# ProProject__PCB_2024-01-29.net
KiCad netlist of a schematic drawn in EasyEDA Pro
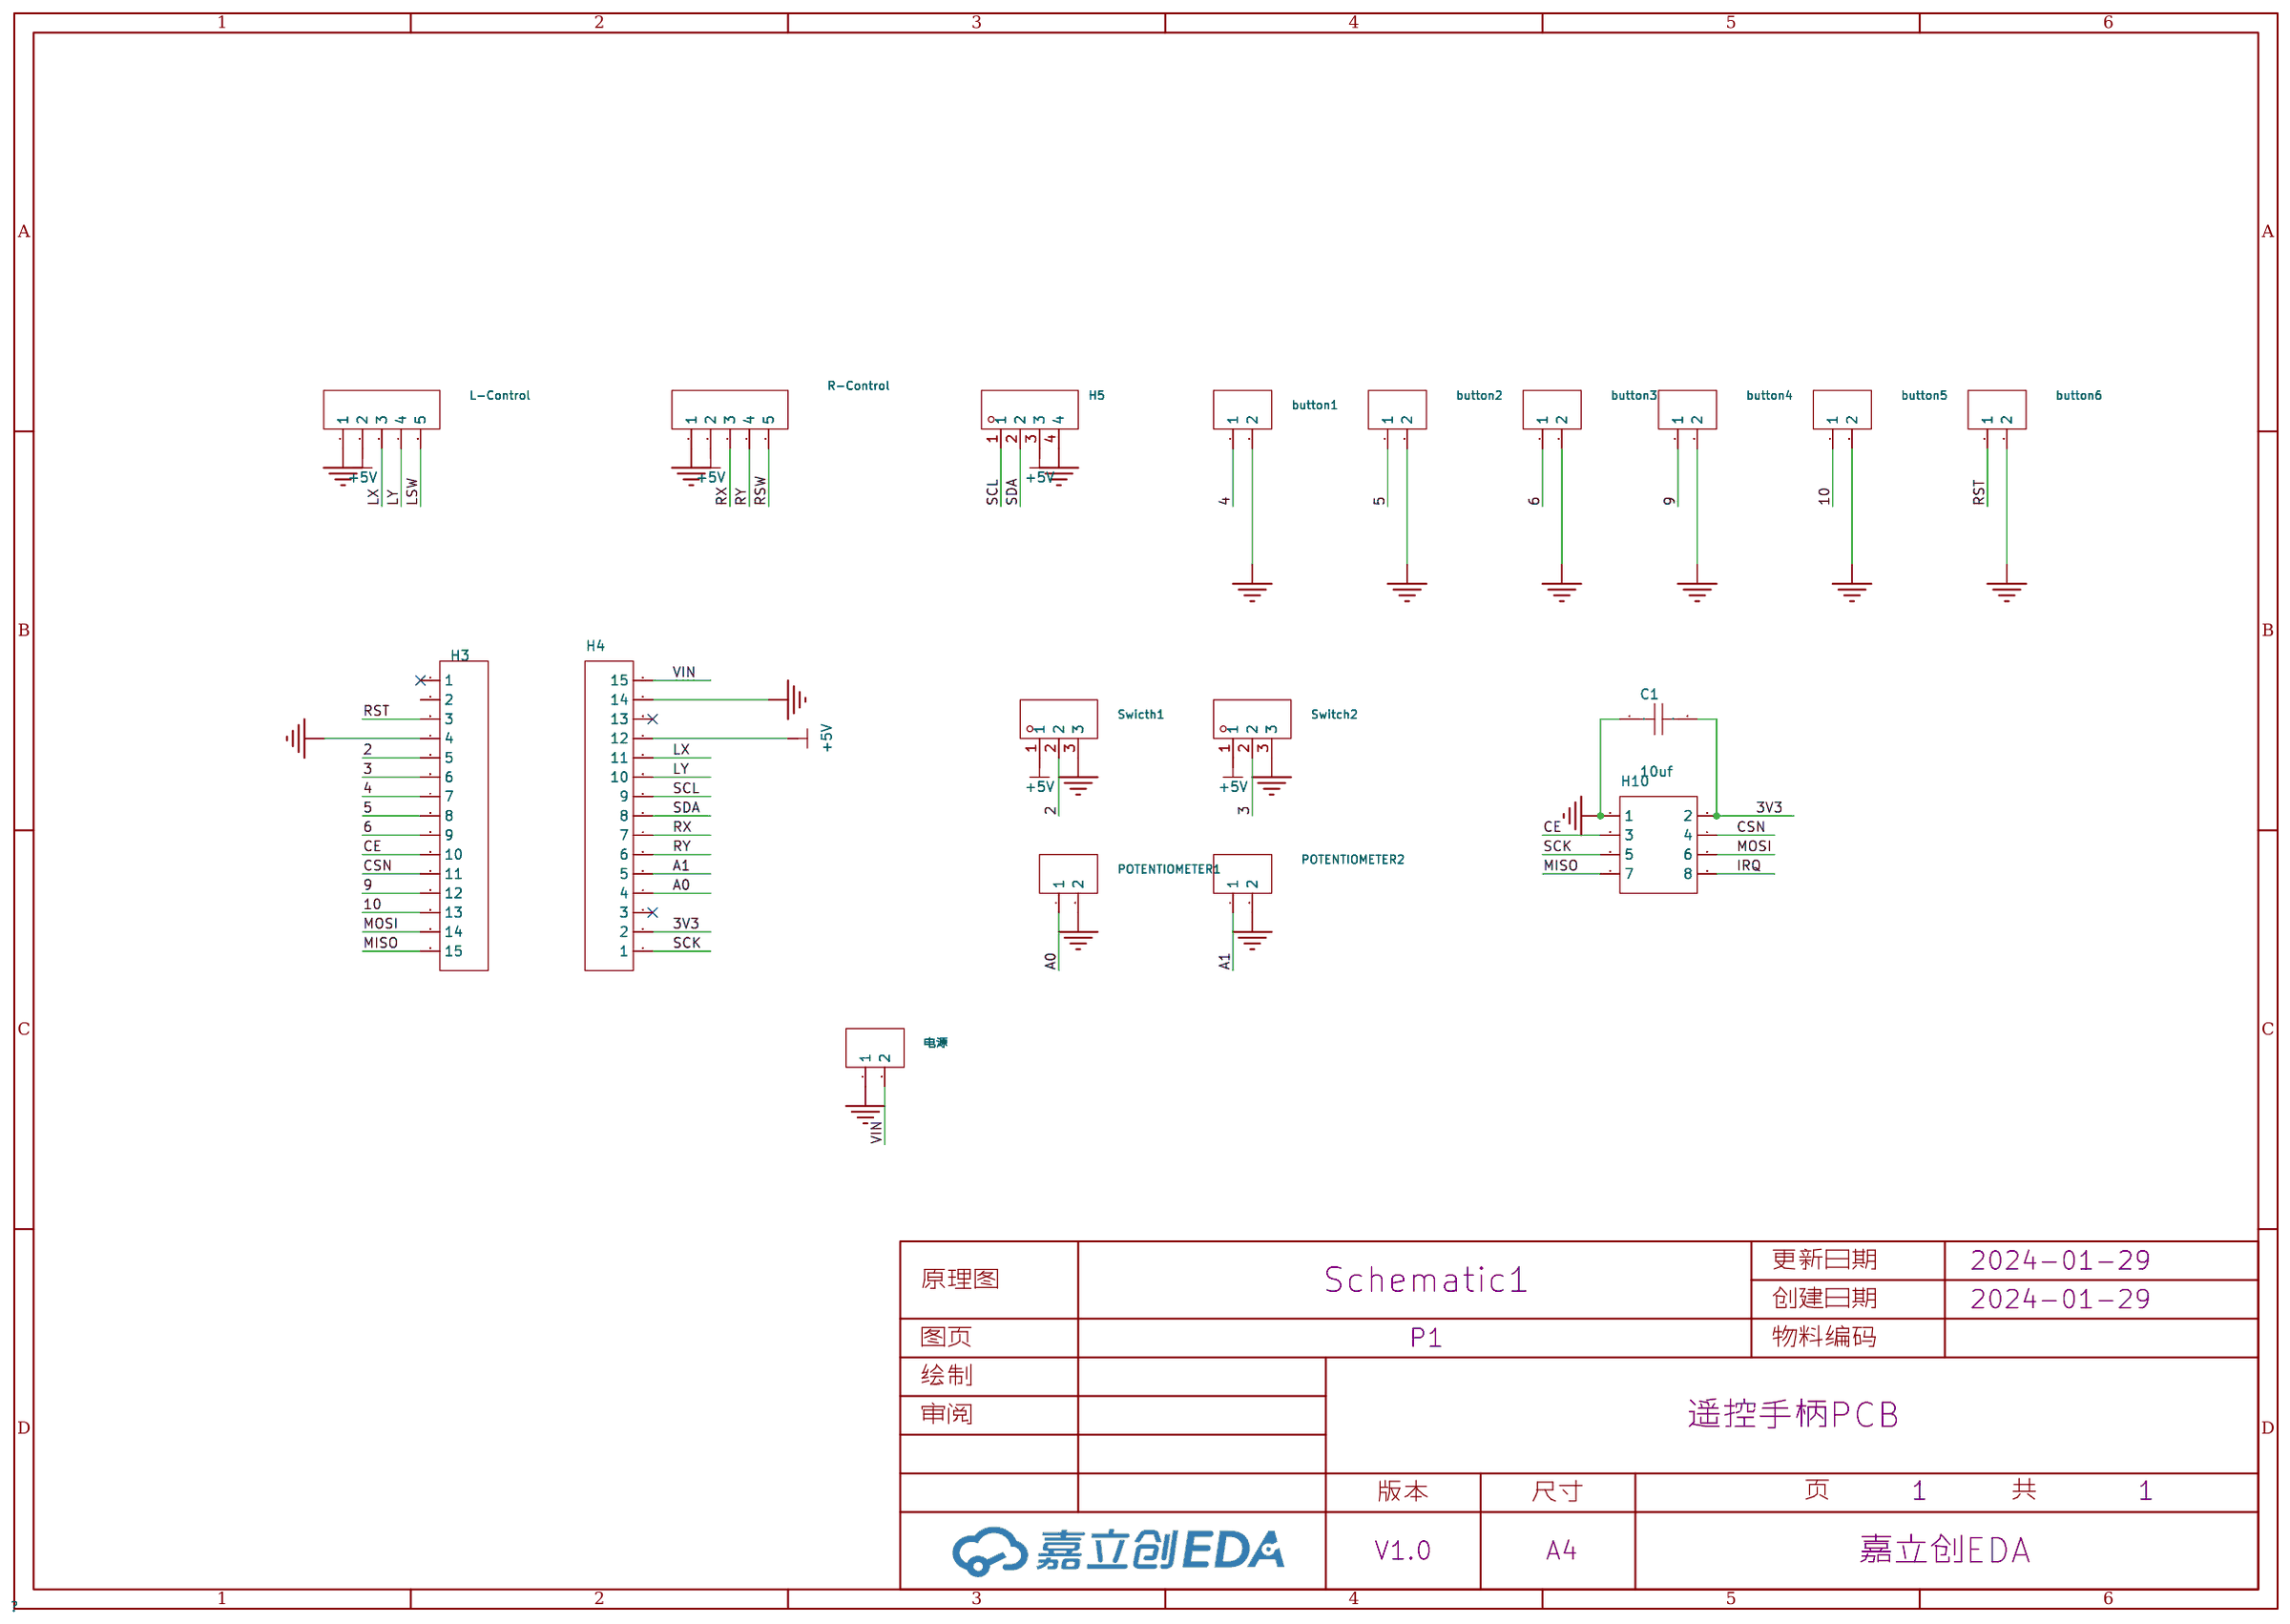
[diagram p0: schematic sheet]

(export (version "E")
  (design (tool "Eeschema 10.0.6"))
  (components
    (comp (ref "button1")
      (value "~")
      (footprint "easyedapro:HDR-TH_2P-P2.54-V-F")
      (libsource (lib "easyedapro") (part "Header-Female-2.54_1x2"))
    )
    (comp (ref "button2")
      (value "~")
      (footprint "easyedapro:HDR-TH_2P-P2.54-V-F")
      (libsource (lib "easyedapro") (part "Header-Female-2.54_1x2"))
    )
    (comp (ref "button3")
      (value "~")
      (footprint "easyedapro:HDR-TH_2P-P2.54-V-F")
      (libsource (lib "easyedapro") (part "Header-Female-2.54_1x2"))
    )
    (comp (ref "button4")
      (value "~")
      (footprint "easyedapro:HDR-TH_2P-P2.54-V-F")
      (libsource (lib "easyedapro") (part "Header-Female-2.54_1x2"))
    )
    (comp (ref "button5")
      (value "~")
      (footprint "easyedapro:HDR-TH_2P-P2.54-V-F")
      (libsource (lib "easyedapro") (part "Header-Female-2.54_1x2"))
    )
    (comp (ref "button6")
      (value "~")
      (footprint "easyedapro:HDR-TH_2P-P2.54-V-F")
      (libsource (lib "easyedapro") (part "Header-Female-2.54_1x2"))
    )
    (comp (ref "C1")
      (value "10uf")
      (footprint "easyedapro:C0805")
      (libsource (lib "easyedapro") (part "CapAcitance"))
    )
    (comp (ref "H3")
      (value "~")
      (footprint "easyedapro:HDR-TH_15P-P2.54-V-F-1")
      (libsource (lib "easyedapro") (part "HDR-F_2.54_1x15P"))
    )
    (comp (ref "H4")
      (value "~")
      (footprint "easyedapro:HDR-TH_15P-P2.54-V-F-1")
      (libsource (lib "easyedapro") (part "HDR-F_2.54_1x15P"))
    )
    (comp (ref "H5")
      (value "~")
      (footprint "easyedapro:HDR-TH_4P-P2.54-V-F")
      (libsource (lib "easyedapro") (part "2.54-1*4P母"))
    )
    (comp (ref "H10")
      (value "~")
      (footprint "easyedapro:HDR-TH_8P-P2.54-V-F-R2-C4-S2.54-1")
      (libsource (lib "easyedapro") (part "HDR-F-2.54_2x4"))
    )
    (comp (ref "L-Control")
      (value "~")
      (footprint "easyedapro:HDR-TH_5P-P2.54-V-F")
      (libsource (lib "easyedapro") (part "Header-Female-2.54_1x5"))
    )
    (comp (ref "POTENTIOMETER1")
      (value "~")
      (footprint "easyedapro:HDR-TH_2P-P2.54-V-F")
      (libsource (lib "easyedapro") (part "Header-Female-2.54_1x2"))
    )
    (comp (ref "POTENTIOMETER2")
      (value "~")
      (footprint "easyedapro:HDR-TH_2P-P2.54-V-F")
      (libsource (lib "easyedapro") (part "Header-Female-2.54_1x2"))
    )
    (comp (ref "R-Control")
      (value "~")
      (footprint "easyedapro:HDR-TH_5P-P2.54-V-F")
      (libsource (lib "easyedapro") (part "Header-Female-2.54_1x5"))
    )
    (comp (ref "Swicth1")
      (value "~")
      (footprint "easyedapro:HDR-TH_3P-P2.54-V-F")
      (libsource (lib "easyedapro") (part "PM254V-11-03-H85"))
    )
    (comp (ref "Switch2")
      (value "~")
      (footprint "easyedapro:HDR-TH_3P-P2.54-V-F")
      (libsource (lib "easyedapro") (part "PM254V-11-03-H85"))
    )
    (comp (ref "电源")
      (value "~")
      (footprint "easyedapro:HDR-TH_2P-P2.54-V-F")
      (libsource (lib "easyedapro") (part "Header-Female-2.54_1x2"))
    )
  )
  (nets
    (net (code "1") (name "+5V") (class "Default")
      (node (ref "H4") (pin "12") (pinfunction "12_12") (pintype "input"))
      (node (ref "H5") (pin "3") (pinfunction "3_3") (pintype "input"))
      (node (ref "L-Control") (pin "2") (pinfunction "2_2") (pintype "input"))
      (node (ref "R-Control") (pin "2") (pinfunction "2_2") (pintype "input"))
      (node (ref "Swicth1") (pin "1") (pinfunction "1_1") (pintype "input"))
      (node (ref "Switch2") (pin "1") (pinfunction "1_1") (pintype "input"))
    )
    (net (code "2") (name "/2") (class "Default")
      (node (ref "H3") (pin "5") (pinfunction "5_5") (pintype "input"))
      (node (ref "Swicth1") (pin "2") (pinfunction "2_2") (pintype "input"))
    )
    (net (code "3") (name "/3") (class "Default")
      (node (ref "H3") (pin "6") (pinfunction "6_6") (pintype "input"))
      (node (ref "Switch2") (pin "2") (pinfunction "2_2") (pintype "input"))
    )
    (net (code "4") (name "/3V3") (class "Default")
      (node (ref "C1") (pin "2") (pinfunction "2_2") (pintype "input"))
      (node (ref "H10") (pin "2") (pinfunction "2_2") (pintype "input"))
      (node (ref "H4") (pin "2") (pinfunction "2_2") (pintype "input"))
    )
    (net (code "5") (name "/4") (class "Default")
      (node (ref "H3") (pin "7") (pinfunction "7_7") (pintype "input"))
      (node (ref "button1") (pin "1") (pinfunction "1_1") (pintype "input"))
    )
    (net (code "6") (name "/5") (class "Default")
      (node (ref "H3") (pin "8") (pinfunction "8_8") (pintype "input"))
      (node (ref "button2") (pin "1") (pinfunction "1_1") (pintype "input"))
    )
    (net (code "7") (name "/6") (class "Default")
      (node (ref "H3") (pin "9") (pinfunction "9_9") (pintype "input"))
      (node (ref "button3") (pin "1") (pinfunction "1_1") (pintype "input"))
    )
    (net (code "8") (name "/9") (class "Default")
      (node (ref "H3") (pin "12") (pinfunction "12_12") (pintype "input"))
      (node (ref "button4") (pin "1") (pinfunction "1_1") (pintype "input"))
    )
    (net (code "9") (name "/10") (class "Default")
      (node (ref "H3") (pin "13") (pinfunction "13_13") (pintype "input"))
      (node (ref "button5") (pin "1") (pinfunction "1_1") (pintype "input"))
    )
    (net (code "10") (name "/A0") (class "Default")
      (node (ref "H4") (pin "4") (pinfunction "4_4") (pintype "input"))
      (node (ref "POTENTIOMETER1") (pin "1") (pinfunction "1_1") (pintype "input"))
    )
    (net (code "11") (name "/A1") (class "Default")
      (node (ref "H4") (pin "5") (pinfunction "5_5") (pintype "input"))
      (node (ref "POTENTIOMETER2") (pin "1") (pinfunction "1_1") (pintype "input"))
    )
    (net (code "12") (name "/CE") (class "Default")
      (node (ref "H10") (pin "3") (pinfunction "3_3") (pintype "input"))
      (node (ref "H3") (pin "10") (pinfunction "10_10") (pintype "input"))
    )
    (net (code "13") (name "/CSN") (class "Default")
      (node (ref "H10") (pin "4") (pinfunction "4_4") (pintype "input"))
      (node (ref "H3") (pin "11") (pinfunction "11_11") (pintype "input"))
    )
    (net (code "14") (name "/IRQ") (class "Default")
      (node (ref "H10") (pin "8") (pinfunction "8_8") (pintype "input"))
    )
    (net (code "15") (name "/LSW") (class "Default")
      (node (ref "L-Control") (pin "5") (pinfunction "5_5") (pintype "input"))
    )
    (net (code "16") (name "/LX") (class "Default")
      (node (ref "H4") (pin "11") (pinfunction "11_11") (pintype "input"))
      (node (ref "L-Control") (pin "3") (pinfunction "3_3") (pintype "input"))
    )
    (net (code "17") (name "/LY") (class "Default")
      (node (ref "H4") (pin "10") (pinfunction "10_10") (pintype "input"))
      (node (ref "L-Control") (pin "4") (pinfunction "4_4") (pintype "input"))
    )
    (net (code "18") (name "/MISO") (class "Default")
      (node (ref "H10") (pin "7") (pinfunction "7_7") (pintype "input"))
      (node (ref "H3") (pin "15") (pinfunction "15_15") (pintype "input"))
    )
    (net (code "19") (name "/MOSI") (class "Default")
      (node (ref "H10") (pin "6") (pinfunction "6_6") (pintype "input"))
      (node (ref "H3") (pin "14") (pinfunction "14_14") (pintype "input"))
    )
    (net (code "20") (name "/RST") (class "Default")
      (node (ref "H3") (pin "3") (pinfunction "3_3") (pintype "input"))
      (node (ref "button6") (pin "1") (pinfunction "1_1") (pintype "input"))
    )
    (net (code "21") (name "/RSW") (class "Default")
      (node (ref "R-Control") (pin "5") (pinfunction "5_5") (pintype "input"))
    )
    (net (code "22") (name "/RX") (class "Default")
      (node (ref "H4") (pin "7") (pinfunction "7_7") (pintype "input"))
      (node (ref "R-Control") (pin "3") (pinfunction "3_3") (pintype "input"))
    )
    (net (code "23") (name "/RY") (class "Default")
      (node (ref "H4") (pin "6") (pinfunction "6_6") (pintype "input"))
      (node (ref "R-Control") (pin "4") (pinfunction "4_4") (pintype "input"))
    )
    (net (code "24") (name "/SCK") (class "Default")
      (node (ref "H10") (pin "5") (pinfunction "5_5") (pintype "input"))
      (node (ref "H4") (pin "1") (pinfunction "1_1") (pintype "input"))
    )
    (net (code "25") (name "/SCL") (class "Default")
      (node (ref "H4") (pin "9") (pinfunction "9_9") (pintype "input"))
      (node (ref "H5") (pin "1") (pinfunction "1_1") (pintype "input"))
    )
    (net (code "26") (name "/SDA") (class "Default")
      (node (ref "H4") (pin "8") (pinfunction "8_8") (pintype "input"))
      (node (ref "H5") (pin "2") (pinfunction "2_2") (pintype "input"))
    )
    (net (code "27") (name "/VIN") (class "Default")
      (node (ref "H4") (pin "15") (pinfunction "15_15") (pintype "input"))
      (node (ref "电源") (pin "2") (pinfunction "2_2") (pintype "input"))
    )
    (net (code "28") (name "GND") (class "Default")
      (node (ref "C1") (pin "1") (pinfunction "1_1") (pintype "input"))
      (node (ref "H10") (pin "1") (pinfunction "1_1") (pintype "input"))
      (node (ref "H3") (pin "4") (pinfunction "4_4") (pintype "input"))
      (node (ref "H4") (pin "14") (pinfunction "14_14") (pintype "input"))
      (node (ref "H5") (pin "4") (pinfunction "4_4") (pintype "input"))
      (node (ref "L-Control") (pin "1") (pinfunction "1_1") (pintype "input"))
      (node (ref "POTENTIOMETER1") (pin "2") (pinfunction "2_2") (pintype "input"))
      (node (ref "POTENTIOMETER2") (pin "2") (pinfunction "2_2") (pintype "input"))
      (node (ref "R-Control") (pin "1") (pinfunction "1_1") (pintype "input"))
      (node (ref "Swicth1") (pin "3") (pinfunction "3_3") (pintype "input"))
      (node (ref "Switch2") (pin "3") (pinfunction "3_3") (pintype "input"))
      (node (ref "button1") (pin "2") (pinfunction "2_2") (pintype "input"))
      (node (ref "button2") (pin "2") (pinfunction "2_2") (pintype "input"))
      (node (ref "button3") (pin "2") (pinfunction "2_2") (pintype "input"))
      (node (ref "button4") (pin "2") (pinfunction "2_2") (pintype "input"))
      (node (ref "button5") (pin "2") (pinfunction "2_2") (pintype "input"))
      (node (ref "button6") (pin "2") (pinfunction "2_2") (pintype "input"))
      (node (ref "电源") (pin "1") (pinfunction "1_1") (pintype "input"))
    )
    (net (code "29") (name "unconnected-(H3-Pad1)") (class "Default")
      (node (ref "H3") (pin "1") (pinfunction "1_1") (pintype "input+no_connect"))
    )
    (net (code "30") (name "unconnected-(H3-Pad2)") (class "Default")
      (node (ref "H3") (pin "2") (pinfunction "2_2") (pintype "input"))
    )
    (net (code "31") (name "unconnected-(H4-Pad3)") (class "Default")
      (node (ref "H4") (pin "3") (pinfunction "3_3") (pintype "input+no_connect"))
    )
    (net (code "32") (name "unconnected-(H4-Pad13)") (class "Default")
      (node (ref "H4") (pin "13") (pinfunction "13_13") (pintype "input+no_connect"))
    )
  )
)
